# CEM3310_VADSR_v2_2.net
KiCad netlist of a schematic drawn in EAGLE
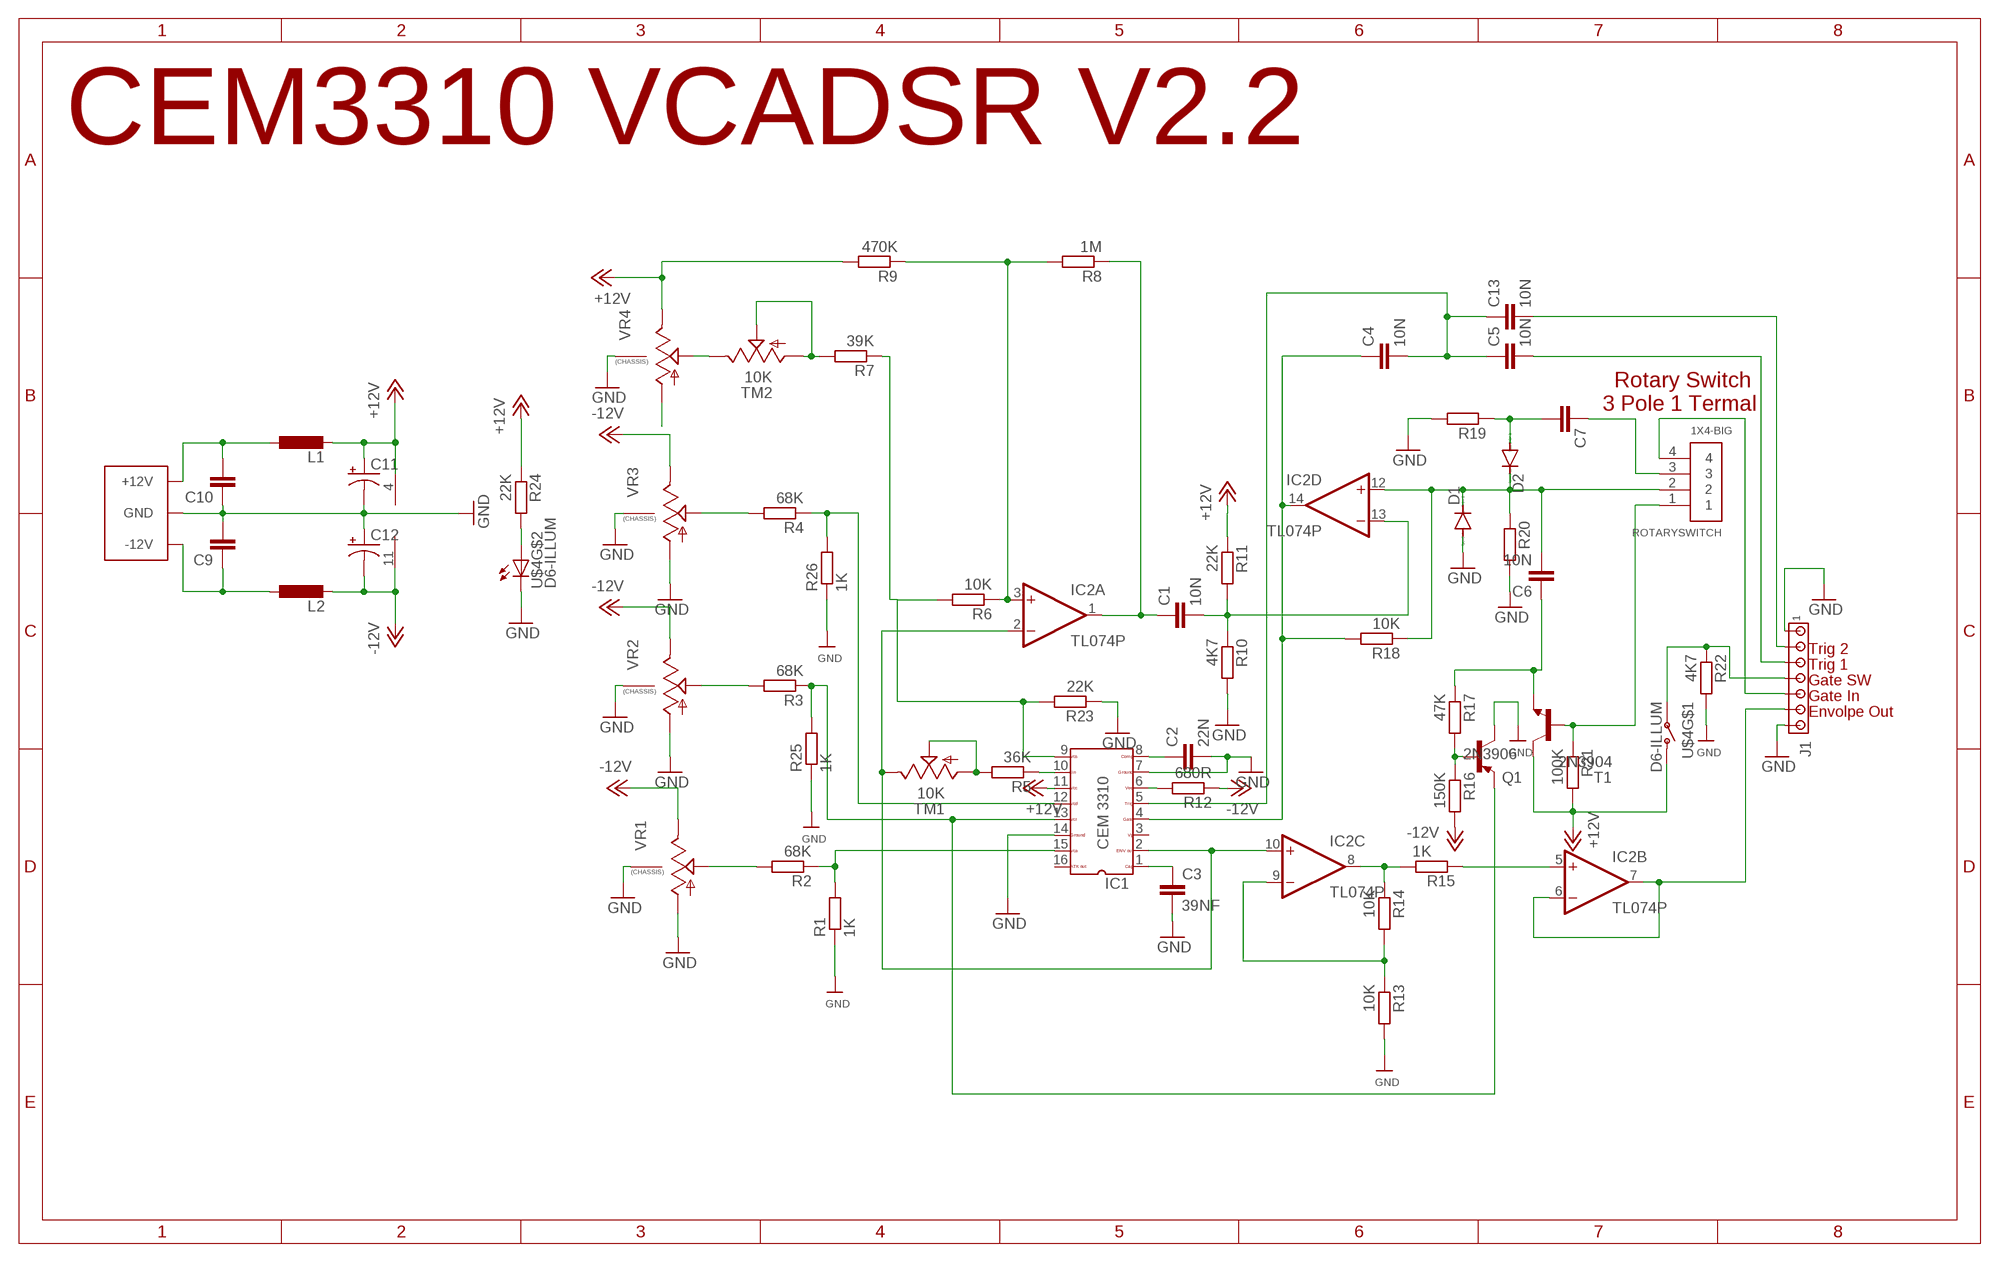
[diagram p0: schematic, sheet 1]

(export (version "E")
  (design (tool "Eeschema 10.0.6"))
  (components
    (comp (ref "C1")
      (value "10N")
      (footprint "eagle-import:C050-025X075")
      (libsource (lib "eagle-import") (part "C-EU050-025X075"))
    )
    (comp (ref "C2")
      (value "22N")
      (footprint "eagle-import:C050-025X075")
      (libsource (lib "eagle-import") (part "C-EU050-025X075"))
    )
    (comp (ref "C3")
      (value "39NF")
      (footprint "eagle-import:C050-025X075")
      (libsource (lib "eagle-import") (part "C-EU050-025X075"))
    )
    (comp (ref "C4")
      (value "10N")
      (footprint "eagle-import:C050-025X075")
      (libsource (lib "eagle-import") (part "C-EU050-025X075"))
    )
    (comp (ref "C5")
      (value "10N")
      (footprint "eagle-import:C050-025X075")
      (libsource (lib "eagle-import") (part "C-EU050-025X075"))
    )
    (comp (ref "C6")
      (value "10N")
      (footprint "eagle-import:C050-025X075")
      (libsource (lib "eagle-import") (part "C-EU050-025X075"))
    )
    (comp (ref "C7")
      (value "C-EU050-025X075")
      (footprint "eagle-import:C050-025X075")
      (libsource (lib "eagle-import") (part "C-EU050-025X075"))
    )
    (comp (ref "C8")
      (value "EURO_POWER_LOCKSKINNY")
      (footprint "eagle-import:EURO_POWER_HEADER")
      (libsource (lib "eagle-import") (part "EURO_POWER_LOCKSKINNY"))
    )
    (comp (ref "C9")
      (value "C-EU050-025X075")
      (footprint "eagle-import:C050-025X075")
      (libsource (lib "eagle-import") (part "C-EU050-025X075"))
    )
    (comp (ref "C10")
      (value "C-EU050-025X075")
      (footprint "eagle-import:C050-025X075")
      (libsource (lib "eagle-import") (part "C-EU050-025X075"))
    )
    (comp (ref "C11")
      (value "CAPACITOR-PE2.5-6")
      (footprint "eagle-import:E2,5-6")
      (libsource (lib "eagle-import") (part "CAPACITOR-PE2.5-6"))
    )
    (comp (ref "C12")
      (value "CAPACITOR-PE2.5-6")
      (footprint "eagle-import:E2,5-6")
      (libsource (lib "eagle-import") (part "CAPACITOR-PE2.5-6"))
    )
    (comp (ref "C13")
      (value "10N")
      (footprint "eagle-import:C050-025X075")
      (libsource (lib "eagle-import") (part "C-EU050-025X075"))
    )
    (comp (ref "D1")
      (value "OA95")
      (footprint "eagle-import:DO35-7")
      (libsource (lib "eagle-import") (part "1N4148DO35-7"))
    )
    (comp (ref "D2")
      (value "1N4148DO35-7")
      (footprint "eagle-import:DO35-7")
      (libsource (lib "eagle-import") (part "1N4148DO35-7"))
    )
    (comp (ref "IC1")
      (value "CEM3310")
      (footprint "eagle-import:DIL16")
      (libsource (lib "eagle-import") (part "CEM3310"))
    )
    (comp (ref "IC2")
      (value "TL074P")
      (footprint "eagle-import:DIL14")
      (libsource (lib "eagle-import") (part "TL074P"))
    )
    (comp (ref "J1")
      (value "MTA07-100")
      (footprint "eagle-import:10X07MTA")
      (libsource (lib "eagle-import") (part "MTA07-100"))
    )
    (comp (ref "L1")
      (value "L-EU0207/7")
      (footprint "eagle-import:0207_7")
      (libsource (lib "eagle-import") (part "L-EU0207/7"))
    )
    (comp (ref "L2")
      (value "L-EU0207/7")
      (footprint "eagle-import:0207_7")
      (libsource (lib "eagle-import") (part "L-EU0207/7"))
    )
    (comp (ref "Q1")
      (value "2N3906")
      (footprint "eagle-import:TO92")
      (libsource (lib "eagle-import") (part "2N3906"))
    )
    (comp (ref "R1")
      (value "1K")
      (footprint "eagle-import:0207_7")
      (libsource (lib "eagle-import") (part "R-EU_0207/7"))
    )
    (comp (ref "R2")
      (value "68K")
      (footprint "eagle-import:0207_7")
      (libsource (lib "eagle-import") (part "R-EU_0207/7"))
    )
    (comp (ref "R3")
      (value "68K")
      (footprint "eagle-import:0207_7")
      (libsource (lib "eagle-import") (part "R-EU_0207/7"))
    )
    (comp (ref "R4")
      (value "68K")
      (footprint "eagle-import:0207_7")
      (libsource (lib "eagle-import") (part "R-EU_0207/7"))
    )
    (comp (ref "R5")
      (value "36K")
      (footprint "eagle-import:0207_7")
      (libsource (lib "eagle-import") (part "R-EU_0207/7"))
    )
    (comp (ref "R6")
      (value "10K")
      (footprint "eagle-import:0207_7")
      (libsource (lib "eagle-import") (part "R-EU_0207/7"))
    )
    (comp (ref "R7")
      (value "39K")
      (footprint "eagle-import:0207_7")
      (libsource (lib "eagle-import") (part "R-EU_0207/7"))
    )
    (comp (ref "R8")
      (value "1M")
      (footprint "eagle-import:0207_7")
      (libsource (lib "eagle-import") (part "R-EU_0207/7"))
    )
    (comp (ref "R9")
      (value "470K")
      (footprint "eagle-import:0207_7")
      (libsource (lib "eagle-import") (part "R-EU_0207/7"))
    )
    (comp (ref "R10")
      (value "4K7")
      (footprint "eagle-import:0207_7")
      (libsource (lib "eagle-import") (part "R-EU_0207/7"))
    )
    (comp (ref "R11")
      (value "22K")
      (footprint "eagle-import:0207_7")
      (libsource (lib "eagle-import") (part "R-EU_0207/7"))
    )
    (comp (ref "R12")
      (value "680R")
      (footprint "eagle-import:0207_7")
      (libsource (lib "eagle-import") (part "R-EU_0207/7"))
    )
    (comp (ref "R13")
      (value "10K")
      (footprint "eagle-import:0207_7")
      (libsource (lib "eagle-import") (part "R-EU_0207/7"))
    )
    (comp (ref "R14")
      (value "10K")
      (footprint "eagle-import:0207_7")
      (libsource (lib "eagle-import") (part "R-EU_0207/7"))
    )
    (comp (ref "R15")
      (value "1K")
      (footprint "eagle-import:0207_7")
      (libsource (lib "eagle-import") (part "R-EU_0207/7"))
    )
    (comp (ref "R16")
      (value "150K")
      (footprint "eagle-import:0207_7")
      (libsource (lib "eagle-import") (part "R-EU_0207/7"))
    )
    (comp (ref "R17")
      (value "47K")
      (footprint "eagle-import:0207_7")
      (libsource (lib "eagle-import") (part "R-EU_0207/7"))
    )
    (comp (ref "R18")
      (value "10K")
      (footprint "eagle-import:0207_7")
      (libsource (lib "eagle-import") (part "R-EU_0207/7"))
    )
    (comp (ref "R19")
      (value "R-EU_0207/7")
      (footprint "eagle-import:0207_7")
      (libsource (lib "eagle-import") (part "R-EU_0207/7"))
    )
    (comp (ref "R20")
      (value "R-EU_0207/7")
      (footprint "eagle-import:0207_7")
      (libsource (lib "eagle-import") (part "R-EU_0207/7"))
    )
    (comp (ref "R21")
      (value "100K")
      (footprint "eagle-import:0207_7")
      (libsource (lib "eagle-import") (part "R-EU_0207/7"))
    )
    (comp (ref "R22")
      (value "4K7")
      (footprint "eagle-import:0207_7")
      (libsource (lib "eagle-import") (part "R-EU_0207/7"))
    )
    (comp (ref "R23")
      (value "22K")
      (footprint "eagle-import:0207_7")
      (libsource (lib "eagle-import") (part "R-EU_0207/7"))
    )
    (comp (ref "R24")
      (value "22K")
      (footprint "eagle-import:0207_7")
      (libsource (lib "eagle-import") (part "R-EU_0207/7"))
    )
    (comp (ref "R25")
      (value "1K")
      (footprint "eagle-import:0207_7")
      (libsource (lib "eagle-import") (part "R-EU_0207/7"))
    )
    (comp (ref "R26")
      (value "1K")
      (footprint "eagle-import:0207_7")
      (libsource (lib "eagle-import") (part "R-EU_0207/7"))
    )
    (comp (ref "ROTARYSWITCH")
      (value "1X4-BIG")
      (footprint "eagle-import:1X04-BIG")
      (libsource (lib "eagle-import") (part "1X4-BIG"))
    )
    (comp (ref "T1")
      (value "2N3904")
      (footprint "eagle-import:TO92")
      (libsource (lib "eagle-import") (part "2N3904"))
    )
    (comp (ref "TM1")
      (value "10K")
      (footprint "eagle-import:6MM")
      (libsource (lib "eagle-import") (part "TRIM"))
    )
    (comp (ref "TM2")
      (value "10K")
      (footprint "eagle-import:6MM")
      (libsource (lib "eagle-import") (part "TRIM"))
    )
    (comp (ref "U$4")
      (value "D6-ILLUM")
      (footprint "eagle-import:D6_PUSH_SWITCH_ILLUM")
      (libsource (lib "eagle-import") (part "D6-ILLUM"))
    )
    (comp (ref "VR1")
      (value "9MM_SNAP-IN_POT_CHASSIS")
      (footprint "eagle-import:9MM_SNAP-IN_POT")
      (libsource (lib "eagle-import") (part "9MM_SNAP-IN_POT_CHASSIS"))
    )
    (comp (ref "VR2")
      (value "9MM_SNAP-IN_POT_CHASSIS")
      (footprint "eagle-import:9MM_SNAP-IN_POT")
      (libsource (lib "eagle-import") (part "9MM_SNAP-IN_POT_CHASSIS"))
    )
    (comp (ref "VR3")
      (value "9MM_SNAP-IN_POT_CHASSIS")
      (footprint "eagle-import:9MM_SNAP-IN_POT")
      (libsource (lib "eagle-import") (part "9MM_SNAP-IN_POT_CHASSIS"))
    )
    (comp (ref "VR4")
      (value "9MM_SNAP-IN_POT_CHASSIS")
      (footprint "eagle-import:9MM_SNAP-IN_POT")
      (libsource (lib "eagle-import") (part "9MM_SNAP-IN_POT_CHASSIS"))
    )
  )
  (nets
    (net (code "1") (name "+12V") (class "Default")
      (node (ref "C11") (pin "+") (pinfunction "+_+") (pintype "passive"))
      (node (ref "IC1") (pin "11") (pinfunction "11_11") (pintype "power_in"))
      (node (ref "IC2") (pin "4") (pinfunction "V+_4") (pintype "power_in"))
      (node (ref "L1") (pin "2") (pinfunction "2_2") (pintype "passive"))
      (node (ref "R11") (pin "1") (pinfunction "1_1") (pintype "passive"))
      (node (ref "R21") (pin "2") (pinfunction "2_2") (pintype "passive"))
      (node (ref "R24") (pin "1") (pinfunction "1_1") (pintype "passive"))
      (node (ref "R9") (pin "2") (pinfunction "2_2") (pintype "passive"))
      (node (ref "T1") (pin "1") (pinfunction "C_1") (pintype "passive"))
      (node (ref "U$4") (pin "P$1") (pinfunction "O_P$1") (pintype "passive"))
      (node (ref "U$4") (pin "P$2") (pinfunction "O_P$2") (pintype "passive"))
      (node (ref "VR4") (pin "3") (pinfunction "E_3") (pintype "passive"))
    )
    (net (code "2") (name "-12V") (class "Default")
      (node (ref "C12") (pin "-") (pinfunction "-_-") (pintype "passive"))
      (node (ref "IC2") (pin "11") (pinfunction "V-_11") (pintype "power_in"))
      (node (ref "L2") (pin "2") (pinfunction "2_2") (pintype "passive"))
      (node (ref "R12") (pin "1") (pinfunction "1_1") (pintype "passive"))
      (node (ref "R16") (pin "2") (pinfunction "2_2") (pintype "passive"))
      (node (ref "VR1") (pin "3") (pinfunction "E_3") (pintype "passive"))
      (node (ref "VR2") (pin "3") (pinfunction "E_3") (pintype "passive"))
      (node (ref "VR3") (pin "3") (pinfunction "E_3") (pintype "passive"))
    )
    (net (code "3") (name "GND") (class "Default")
      (node (ref "C10") (pin "1") (pinfunction "1_1") (pintype "passive"))
      (node (ref "C11") (pin "-") (pinfunction "-_-") (pintype "passive"))
      (node (ref "C12") (pin "+") (pinfunction "+_+") (pintype "passive"))
      (node (ref "C2") (pin "2") (pinfunction "2_2") (pintype "passive"))
      (node (ref "C3") (pin "2") (pinfunction "2_2") (pintype "passive"))
      (node (ref "C8") (pin "3") (pinfunction "GND_3") (pintype "bidirectional"))
      (node (ref "C8") (pin "4") (pinfunction "GND_4") (pintype "bidirectional"))
      (node (ref "C8") (pin "5") (pinfunction "GND_5") (pintype "bidirectional"))
      (node (ref "C8") (pin "6") (pinfunction "GND_6") (pintype "bidirectional"))
      (node (ref "C8") (pin "7") (pinfunction "GND_7") (pintype "bidirectional"))
      (node (ref "C8") (pin "8") (pinfunction "GND_8") (pintype "bidirectional"))
      (node (ref "C9") (pin "2") (pinfunction "2_2") (pintype "passive"))
      (node (ref "D1") (pin "A") (pinfunction "A_A") (pintype "passive"))
      (node (ref "IC1") (pin "14") (pinfunction "14_14") (pintype "power_in"))
      (node (ref "IC1") (pin "7") (pinfunction "7_7") (pintype "power_in"))
      (node (ref "J1") (pin "1") (pinfunction "1_1") (pintype "passive"))
      (node (ref "J1") (pin "7") (pinfunction "7_7") (pintype "passive"))
      (node (ref "Q1") (pin "1") (pinfunction "C_1") (pintype "passive"))
      (node (ref "R1") (pin "1") (pinfunction "1_1") (pintype "passive"))
      (node (ref "R10") (pin "2") (pinfunction "2_2") (pintype "passive"))
      (node (ref "R13") (pin "2") (pinfunction "2_2") (pintype "passive"))
      (node (ref "R19") (pin "2") (pinfunction "2_2") (pintype "passive"))
      (node (ref "R20") (pin "2") (pinfunction "2_2") (pintype "passive"))
      (node (ref "R22") (pin "2") (pinfunction "2_2") (pintype "passive"))
      (node (ref "R23") (pin "1") (pinfunction "1_1") (pintype "passive"))
      (node (ref "R25") (pin "1") (pinfunction "1_1") (pintype "passive"))
      (node (ref "R26") (pin "1") (pinfunction "1_1") (pintype "passive"))
      (node (ref "U$4") (pin "LED-") (pinfunction "C_LED-") (pintype "passive"))
      (node (ref "VR1") (pin "1") (pinfunction "A_1") (pintype "passive"))
      (node (ref "VR1") (pin "CHASSIS1") (pinfunction "P$1_CHASSIS1") (pintype "passive"))
      (node (ref "VR1") (pin "CHASSIS2") (pinfunction "P$1_CHASSIS2") (pintype "passive"))
      (node (ref "VR2") (pin "1") (pinfunction "A_1") (pintype "passive"))
      (node (ref "VR2") (pin "CHASSIS1") (pinfunction "P$1_CHASSIS1") (pintype "passive"))
      (node (ref "VR2") (pin "CHASSIS2") (pinfunction "P$1_CHASSIS2") (pintype "passive"))
      (node (ref "VR3") (pin "1") (pinfunction "A_1") (pintype "passive"))
      (node (ref "VR3") (pin "CHASSIS1") (pinfunction "P$1_CHASSIS1") (pintype "passive"))
      (node (ref "VR3") (pin "CHASSIS2") (pinfunction "P$1_CHASSIS2") (pintype "passive"))
      (node (ref "VR4") (pin "CHASSIS1") (pinfunction "P$1_CHASSIS1") (pintype "passive"))
      (node (ref "VR4") (pin "CHASSIS2") (pinfunction "P$1_CHASSIS2") (pintype "passive"))
    )
    (net (code "4") (name "Net-(C2-Pad1)") (class "Default")
      (node (ref "C2") (pin "1") (pinfunction "1_1") (pintype "passive"))
      (node (ref "IC1") (pin "8") (pinfunction "8_8") (pintype "bidirectional"))
    )
    (net (code "5") (name "Net-(C3-Pad1)") (class "Default")
      (node (ref "C3") (pin "1") (pinfunction "1_1") (pintype "passive"))
      (node (ref "IC1") (pin "1") (pinfunction "1_1") (pintype "bidirectional"))
    )
    (net (code "6") (name "Net-(C5-Pad2)") (class "Default")
      (node (ref "C5") (pin "2") (pinfunction "2_2") (pintype "passive"))
      (node (ref "J1") (pin "3") (pinfunction "3_3") (pintype "passive"))
    )
    (net (code "7") (name "Net-(C7-Pad1)") (class "Default")
      (node (ref "C7") (pin "1") (pinfunction "1_1") (pintype "passive"))
      (node (ref "ROTARYSWITCH") (pin "3") (pinfunction "3_3") (pintype "bidirectional"))
    )
    (net (code "8") (name "Net-(C7-Pad2)") (class "Default")
      (node (ref "C7") (pin "2") (pinfunction "2_2") (pintype "passive"))
      (node (ref "D2") (pin "A") (pinfunction "A_A") (pintype "passive"))
      (node (ref "R19") (pin "1") (pinfunction "1_1") (pintype "passive"))
    )
    (net (code "9") (name "Net-(C8--12V-Pad1)") (class "Default")
      (node (ref "C8") (pin "1") (pinfunction "-12V_1") (pintype "bidirectional"))
      (node (ref "C8") (pin "2") (pinfunction "-12V_2") (pintype "bidirectional"))
      (node (ref "C9") (pin "1") (pinfunction "1_1") (pintype "passive"))
      (node (ref "L2") (pin "1") (pinfunction "1_1") (pintype "passive"))
    )
    (net (code "10") (name "Net-(C10-Pad2)") (class "Default")
      (node (ref "C10") (pin "2") (pinfunction "2_2") (pintype "passive"))
      (node (ref "C8") (pin "10") (pinfunction "+12V_10") (pintype "bidirectional"))
      (node (ref "C8") (pin "9") (pinfunction "+12V_9") (pintype "bidirectional"))
      (node (ref "L1") (pin "1") (pinfunction "1_1") (pintype "passive"))
    )
    (net (code "11") (name "Net-(C13-Pad1)") (class "Default")
      (node (ref "C13") (pin "1") (pinfunction "1_1") (pintype "passive"))
      (node (ref "C4") (pin "2") (pinfunction "2_2") (pintype "passive"))
      (node (ref "C5") (pin "1") (pinfunction "1_1") (pintype "passive"))
      (node (ref "IC1") (pin "5") (pinfunction "5_5") (pintype "input"))
    )
    (net (code "12") (name "Net-(C13-Pad2)") (class "Default")
      (node (ref "C13") (pin "2") (pinfunction "2_2") (pintype "passive"))
      (node (ref "J1") (pin "2") (pinfunction "2_2") (pintype "passive"))
    )
    (net (code "13") (name "Net-(IC1-Pad6)") (class "Default")
      (node (ref "IC1") (pin "6") (pinfunction "6_6") (pintype "power_in"))
      (node (ref "R12") (pin "2") (pinfunction "2_2") (pintype "passive"))
    )
    (net (code "14") (name "Net-(IC1-Pad9)") (class "Default")
      (node (ref "IC1") (pin "9") (pinfunction "9_9") (pintype "power_in"))
      (node (ref "R23") (pin "2") (pinfunction "2_2") (pintype "passive"))
      (node (ref "R6") (pin "2") (pinfunction "2_2") (pintype "passive"))
      (node (ref "R7") (pin "1") (pinfunction "1_1") (pintype "passive"))
    )
    (net (code "15") (name "Net-(IC1-Pad10)") (class "Default")
      (node (ref "IC1") (pin "10") (pinfunction "10_10") (pintype "power_in"))
      (node (ref "R5") (pin "1") (pinfunction "1_1") (pintype "passive"))
    )
    (net (code "16") (name "Net-(IC1-Pad12)") (class "Default")
      (node (ref "IC1") (pin "12") (pinfunction "12_12") (pintype "power_in"))
      (node (ref "R26") (pin "2") (pinfunction "2_2") (pintype "passive"))
      (node (ref "R4") (pin "1") (pinfunction "1_1") (pintype "passive"))
    )
    (net (code "17") (name "Net-(IC1-Pad15)") (class "Default")
      (node (ref "IC1") (pin "15") (pinfunction "15_15") (pintype "power_in"))
      (node (ref "R1") (pin "2") (pinfunction "2_2") (pintype "passive"))
      (node (ref "R2") (pin "1") (pinfunction "1_1") (pintype "passive"))
    )
    (net (code "18") (name "Net-(IC2A-+IN)") (class "Default")
      (node (ref "IC2") (pin "3") (pinfunction "+IN_3") (pintype "input"))
      (node (ref "R6") (pin "1") (pinfunction "1_1") (pintype "passive"))
      (node (ref "R8") (pin "2") (pinfunction "2_2") (pintype "passive"))
      (node (ref "R9") (pin "1") (pinfunction "1_1") (pintype "passive"))
    )
    (net (code "19") (name "Net-(IC2A--IN)") (class "Default")
      (node (ref "IC1") (pin "2") (pinfunction "2_2") (pintype "output"))
      (node (ref "IC2") (pin "10") (pinfunction "+IN_10") (pintype "input"))
      (node (ref "IC2") (pin "2") (pinfunction "-IN_2") (pintype "input"))
      (node (ref "TM1") (pin "E") (pinfunction "E_E") (pintype "passive"))
    )
    (net (code "20") (name "Net-(IC2A-OUT)") (class "Default")
      (node (ref "C1") (pin "1") (pinfunction "1_1") (pintype "passive"))
      (node (ref "IC2") (pin "1") (pinfunction "OUT_1") (pintype "output"))
      (node (ref "R8") (pin "1") (pinfunction "1_1") (pintype "passive"))
    )
    (net (code "21") (name "Net-(IC2B-+IN)") (class "Default")
      (node (ref "IC2") (pin "5") (pinfunction "+IN_5") (pintype "input"))
      (node (ref "R15") (pin "1") (pinfunction "1_1") (pintype "passive"))
    )
    (net (code "22") (name "Net-(IC2B--IN)") (class "Default")
      (node (ref "IC2") (pin "6") (pinfunction "-IN_6") (pintype "input"))
      (node (ref "IC2") (pin "7") (pinfunction "OUT_7") (pintype "output"))
      (node (ref "J1") (pin "6") (pinfunction "6_6") (pintype "passive"))
    )
    (net (code "23") (name "Net-(IC2C--IN)") (class "Default")
      (node (ref "IC2") (pin "9") (pinfunction "-IN_9") (pintype "input"))
      (node (ref "R13") (pin "1") (pinfunction "1_1") (pintype "passive"))
      (node (ref "R14") (pin "2") (pinfunction "2_2") (pintype "passive"))
    )
    (net (code "24") (name "Net-(IC2C-OUT)") (class "Default")
      (node (ref "IC2") (pin "8") (pinfunction "OUT_8") (pintype "output"))
      (node (ref "R14") (pin "1") (pinfunction "1_1") (pintype "passive"))
      (node (ref "R15") (pin "2") (pinfunction "2_2") (pintype "passive"))
    )
    (net (code "25") (name "Net-(IC2D-+IN)") (class "Default")
      (node (ref "C6") (pin "2") (pinfunction "2_2") (pintype "passive"))
      (node (ref "D1") (pin "C") (pinfunction "C_C") (pintype "passive"))
      (node (ref "D2") (pin "C") (pinfunction "C_C") (pintype "passive"))
      (node (ref "IC2") (pin "12") (pinfunction "+IN_12") (pintype "input"))
      (node (ref "R18") (pin "1") (pinfunction "1_1") (pintype "passive"))
      (node (ref "R20") (pin "1") (pinfunction "1_1") (pintype "passive"))
      (node (ref "ROTARYSWITCH") (pin "2") (pinfunction "2_2") (pintype "bidirectional"))
    )
    (net (code "26") (name "Net-(IC2D--IN)") (class "Default")
      (node (ref "C1") (pin "2") (pinfunction "2_2") (pintype "passive"))
      (node (ref "IC2") (pin "13") (pinfunction "-IN_13") (pintype "input"))
      (node (ref "R10") (pin "1") (pinfunction "1_1") (pintype "passive"))
      (node (ref "R11") (pin "2") (pinfunction "2_2") (pintype "passive"))
    )
    (net (code "27") (name "Net-(IC2D-OUT)") (class "Default")
      (node (ref "C4") (pin "1") (pinfunction "1_1") (pintype "passive"))
      (node (ref "IC1") (pin "4") (pinfunction "4_4") (pintype "input"))
      (node (ref "IC2") (pin "14") (pinfunction "OUT_14") (pintype "output"))
      (node (ref "R18") (pin "2") (pinfunction "2_2") (pintype "passive"))
    )
    (net (code "28") (name "Net-(J1-Pad4)") (class "Default")
      (node (ref "J1") (pin "4") (pinfunction "4_4") (pintype "passive"))
      (node (ref "R22") (pin "1") (pinfunction "1_1") (pintype "passive"))
      (node (ref "U$4") (pin "P$3") (pinfunction "P_P$3") (pintype "passive"))
      (node (ref "U$4") (pin "P$4") (pinfunction "P_P$4") (pintype "passive"))
    )
    (net (code "29") (name "Net-(J1-Pad5)") (class "Default")
      (node (ref "J1") (pin "5") (pinfunction "5_5") (pintype "passive"))
      (node (ref "ROTARYSWITCH") (pin "4") (pinfunction "4_4") (pintype "bidirectional"))
    )
    (net (code "30") (name "Net-(Q1-B)") (class "Default")
      (node (ref "Q1") (pin "2") (pinfunction "B_2") (pintype "passive"))
      (node (ref "R16") (pin "1") (pinfunction "1_1") (pintype "passive"))
      (node (ref "R17") (pin "2") (pinfunction "2_2") (pintype "passive"))
    )
    (net (code "31") (name "Net-(Q1-E)") (class "Default")
      (node (ref "IC1") (pin "13") (pinfunction "13_13") (pintype "power_in"))
      (node (ref "Q1") (pin "3") (pinfunction "E_3") (pintype "passive"))
      (node (ref "R25") (pin "2") (pinfunction "2_2") (pintype "passive"))
      (node (ref "R3") (pin "1") (pinfunction "1_1") (pintype "passive"))
    )
    (net (code "32") (name "Net-(R5-Pad2)") (class "Default")
      (node (ref "R5") (pin "2") (pinfunction "2_2") (pintype "passive"))
      (node (ref "TM1") (pin "A") (pinfunction "A_A") (pintype "passive"))
      (node (ref "TM1") (pin "S") (pinfunction "S_S") (pintype "passive"))
    )
    (net (code "33") (name "Net-(R7-Pad2)") (class "Default")
      (node (ref "R7") (pin "2") (pinfunction "2_2") (pintype "passive"))
      (node (ref "TM2") (pin "A") (pinfunction "A_A") (pintype "passive"))
      (node (ref "TM2") (pin "S") (pinfunction "S_S") (pintype "passive"))
    )
    (net (code "34") (name "Net-(T1-B)") (class "Default")
      (node (ref "R21") (pin "1") (pinfunction "1_1") (pintype "passive"))
      (node (ref "ROTARYSWITCH") (pin "1") (pinfunction "1_1") (pintype "bidirectional"))
      (node (ref "T1") (pin "2") (pinfunction "B_2") (pintype "passive"))
    )
    (net (code "35") (name "Net-(T1-E)") (class "Default")
      (node (ref "C6") (pin "1") (pinfunction "1_1") (pintype "passive"))
      (node (ref "R17") (pin "1") (pinfunction "1_1") (pintype "passive"))
      (node (ref "T1") (pin "3") (pinfunction "E_3") (pintype "passive"))
    )
    (net (code "36") (name "Net-(U$4B-A)") (class "Default")
      (node (ref "R24") (pin "2") (pinfunction "2_2") (pintype "passive"))
      (node (ref "U$4") (pin "LED+") (pinfunction "A_LED+") (pintype "passive"))
    )
    (net (code "37") (name "Net-(VR1-S)") (class "Default")
      (node (ref "R2") (pin "2") (pinfunction "2_2") (pintype "passive"))
      (node (ref "VR1") (pin "2") (pinfunction "S_2") (pintype "passive"))
    )
    (net (code "38") (name "Net-(VR2-S)") (class "Default")
      (node (ref "R3") (pin "2") (pinfunction "2_2") (pintype "passive"))
      (node (ref "VR2") (pin "2") (pinfunction "S_2") (pintype "passive"))
    )
    (net (code "39") (name "Net-(VR3-S)") (class "Default")
      (node (ref "R4") (pin "2") (pinfunction "2_2") (pintype "passive"))
      (node (ref "VR3") (pin "2") (pinfunction "S_2") (pintype "passive"))
    )
    (net (code "40") (name "Net-(VR4-S)") (class "Default")
      (node (ref "TM2") (pin "E") (pinfunction "E_E") (pintype "passive"))
      (node (ref "VR4") (pin "2") (pinfunction "S_2") (pintype "passive"))
    )
    (net (code "41") (name "unconnected-(IC1-Pad3)") (class "Default")
      (node (ref "IC1") (pin "3") (pinfunction "3_3") (pintype "bidirectional"))
    )
    (net (code "42") (name "unconnected-(IC1-Pad16)") (class "Default")
      (node (ref "IC1") (pin "16") (pinfunction "16_16") (pintype "output"))
    )
    (net (code "43") (name "unconnected-(VR4-A-Pad1)") (class "Default")
      (node (ref "VR4") (pin "1") (pinfunction "A_1") (pintype "passive"))
    )
  )
)
